# EJ8_LOGIC_SCH.net
KiCad netlist of a schematic drawn in Altium Designer
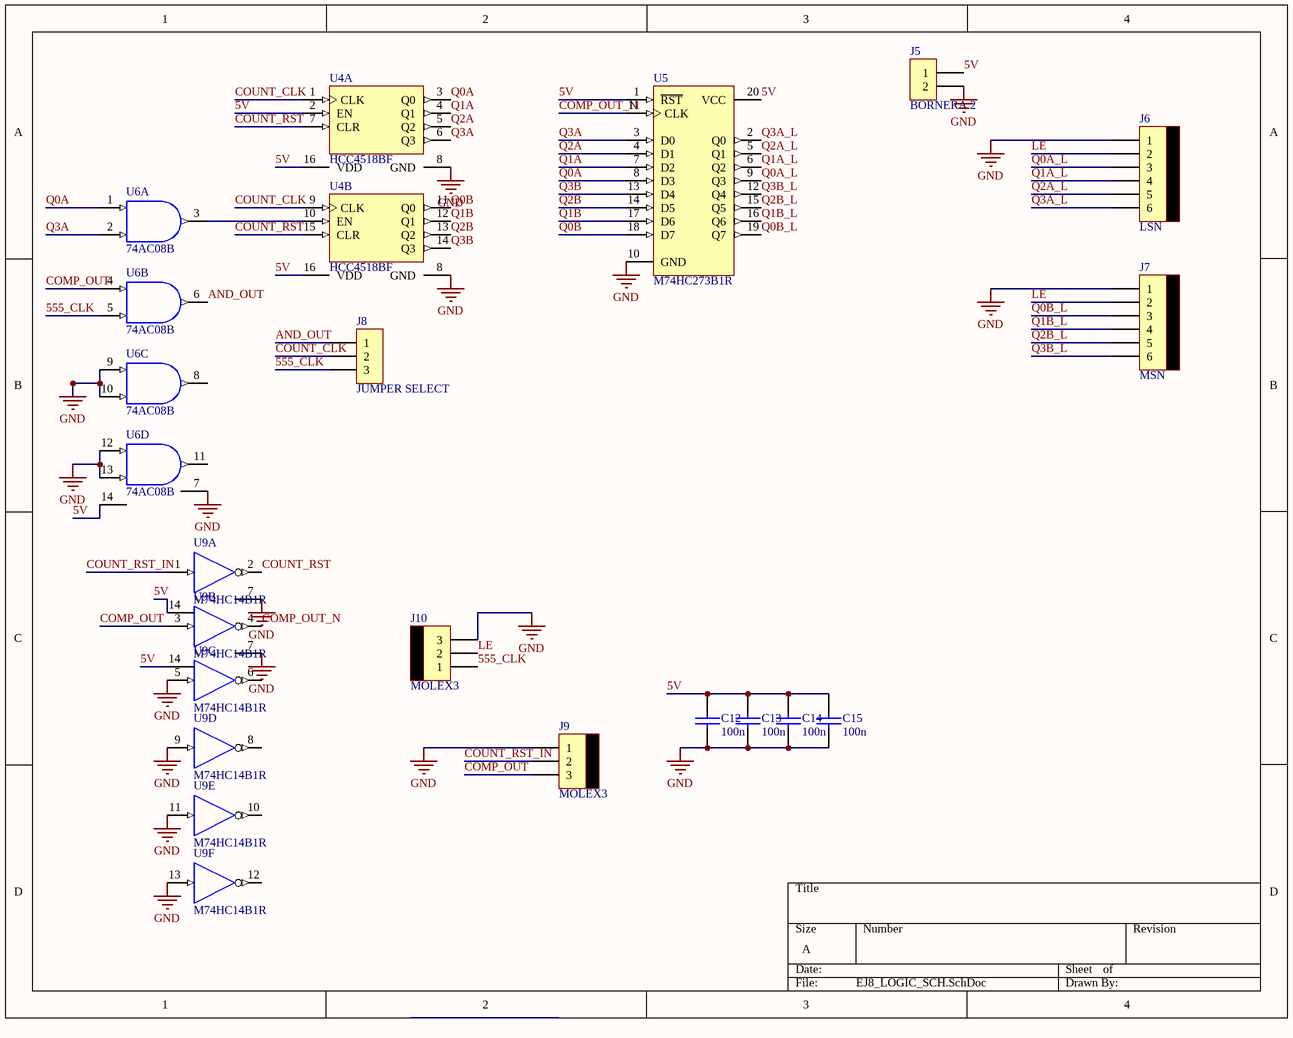
[diagram p0: EJ8_LOGIC_SCH.SchDoc]

(export (version "E")
  (design (tool "Eeschema 10.0.6"))
  (components
    (comp (ref "C12") (value "100n") (footprint "0805") (libsource (lib "LIBEBAL") (part "CAP")))
    (comp (ref "C13") (value "100n") (footprint "0805") (libsource (lib "LIBEBAL") (part "CAP")))
    (comp (ref "C14") (value "100n") (footprint "0805") (libsource (lib "LIBEBAL") (part "CAP")))
    (comp (ref "C15") (value "100n") (footprint "0805") (libsource (lib "LIBEBAL") (part "CAP")))
    (comp (ref "J5")
      (value "BORNERA 2")
      (footprint "BORNERA2")
      (libsource (lib "LIBEBAL") (part "BORNERA 2"))
    )
    (comp (ref "J6") (value "LSN") (footprint "MOLEX6") (libsource (lib "LIBEBAL") (part "MOLEX6")))
    (comp (ref "J7") (value "MSN") (footprint "MOLEX6") (libsource (lib "LIBEBAL") (part "MOLEX6")))
    (comp (ref "J8") (value "JUMPER SELECT") (footprint "SIP3") (libsource (lib "LIBEBAL") (part "CON3")))
    (comp (ref "J9") (value "MOLEX3") (footprint "MOLEX3") (libsource (lib "") (part "MOLEX3_1")))
    (comp (ref "J10") (value "MOLEX3") (footprint "MOLEX3") (libsource (lib "LIBEBAL") (part "MOLEX3")))
    (comp (ref "U4")
      (value "HCC4518BF")
      (footprint "DIP16")
      (description "Dual Decade Up-Counter")
      (fields (field (name "PUBLISHER") "Altium Limited"))
      (libsource (lib "ST Logic Counter") (part "HCC4518BF"))
    )
    (comp (ref "U5")
      (value "M74HC273B1R")
      (footprint "DIP20")
      (description "Octal D-Type Flip-Flop with Clear")
      (fields (field (name "PUBLISHER") "Altium Limited"))
      (libsource (lib "ST Logic Flip-Flop") (part "M74HC273B1R"))
    )
    (comp (ref "U6")
      (value "74AC08B")
      (footprint "DIP14")
      (description "Quad 2-Input AND Gate")
      (fields (field (name "PUBLISHER") "Altium Limited"))
      (libsource (lib "ST Logic Gate") (part "74AC08B"))
    )
    (comp (ref "U9")
      (value "M74HC14B1R")
      (footprint "DIP14")
      (description "Hex Schmitt Inverter")
      (fields (field (name "PUBLISHER") "Altium Limited"))
      (libsource (lib "ST Logic Gate") (part "M74HC14B1R"))
    )
  )
  (nets
    (net (code "1") (name "/555_CLK") (class "Default")
      (node (ref "J10") (pin "1") (pinfunction "1_1") (pintype "passive"))
      (node (ref "J8") (pin "3") (pinfunction "3_3") (pintype "passive"))
      (node (ref "U6") (pin "5") (pinfunction "B_5") (pintype "input"))
    )
    (net (code "2") (name "/AND_OUT") (class "Default")
      (node (ref "J8") (pin "1") (pinfunction "1_1") (pintype "passive"))
      (node (ref "U6") (pin "6") (pinfunction "Y_6") (pintype "output"))
    )
    (net (code "3") (name "/COMP_OUT") (class "Default")
      (node (ref "J9") (pin "3") (pinfunction "3_3") (pintype "passive"))
      (node (ref "U6") (pin "4") (pinfunction "A_4") (pintype "input"))
      (node (ref "U9") (pin "3") (pinfunction "A_3") (pintype "input"))
    )
    (net (code "4") (name "/COMP_OUT_N") (class "Default")
      (node (ref "U5") (pin "11") (pinfunction "CLK_11") (pintype "input"))
      (node (ref "U9") (pin "4") (pinfunction "Y_4") (pintype "output"))
    )
    (net (code "5") (name "/COUNT_CLK") (class "Default")
      (node (ref "J8") (pin "2") (pinfunction "2_2") (pintype "passive"))
      (node (ref "U4") (pin "1") (pinfunction "CLK_1") (pintype "input"))
      (node (ref "U4") (pin "9") (pinfunction "CLK_9") (pintype "input"))
    )
    (net (code "6") (name "/COUNT_RST") (class "Default")
      (node (ref "U4") (pin "15") (pinfunction "CLR_15") (pintype "input"))
      (node (ref "U4") (pin "7") (pinfunction "CLR_7") (pintype "input"))
      (node (ref "U9") (pin "2") (pinfunction "Y_2") (pintype "output"))
    )
    (net (code "7") (name "/COUNT_RST_IN") (class "Default")
      (node (ref "J9") (pin "2") (pinfunction "2_2") (pintype "passive"))
      (node (ref "U9") (pin "1") (pinfunction "A_1") (pintype "input"))
    )
    (net (code "8") (name "/LE") (class "Default")
      (node (ref "J10") (pin "2") (pinfunction "2_2") (pintype "passive"))
      (node (ref "J6") (pin "2") (pinfunction "2_2") (pintype "passive"))
      (node (ref "J7") (pin "2") (pinfunction "2_2") (pintype "passive"))
    )
    (net (code "9") (name "/Q0A") (class "Default")
      (node (ref "U4") (pin "3") (pinfunction "Q0_3") (pintype "output"))
      (node (ref "U5") (pin "8") (pinfunction "D3_8") (pintype "input"))
      (node (ref "U6") (pin "1") (pinfunction "A_1") (pintype "input"))
    )
    (net (code "10") (name "/Q0A_L") (class "Default")
      (node (ref "J6") (pin "3") (pinfunction "3_3") (pintype "passive"))
      (node (ref "U5") (pin "9") (pinfunction "Q3_9") (pintype "output"))
    )
    (net (code "11") (name "/Q0B") (class "Default")
      (node (ref "U4") (pin "11") (pinfunction "Q0_11") (pintype "output"))
      (node (ref "U5") (pin "18") (pinfunction "D7_18") (pintype "input"))
    )
    (net (code "12") (name "/Q0B_L") (class "Default")
      (node (ref "J7") (pin "3") (pinfunction "3_3") (pintype "passive"))
      (node (ref "U5") (pin "19") (pinfunction "Q7_19") (pintype "output"))
    )
    (net (code "13") (name "/Q1A") (class "Default")
      (node (ref "U4") (pin "4") (pinfunction "Q1_4") (pintype "output"))
      (node (ref "U5") (pin "7") (pinfunction "D2_7") (pintype "input"))
    )
    (net (code "14") (name "/Q1A_L") (class "Default")
      (node (ref "J6") (pin "4") (pinfunction "4_4") (pintype "passive"))
      (node (ref "U5") (pin "6") (pinfunction "Q2_6") (pintype "output"))
    )
    (net (code "15") (name "/Q1B") (class "Default")
      (node (ref "U4") (pin "12") (pinfunction "Q1_12") (pintype "output"))
      (node (ref "U5") (pin "17") (pinfunction "D6_17") (pintype "input"))
    )
    (net (code "16") (name "/Q1B_L") (class "Default")
      (node (ref "J7") (pin "4") (pinfunction "4_4") (pintype "passive"))
      (node (ref "U5") (pin "16") (pinfunction "Q6_16") (pintype "output"))
    )
    (net (code "17") (name "/Q2A") (class "Default")
      (node (ref "U4") (pin "5") (pinfunction "Q2_5") (pintype "output"))
      (node (ref "U5") (pin "4") (pinfunction "D1_4") (pintype "input"))
    )
    (net (code "18") (name "/Q2A_L") (class "Default")
      (node (ref "J6") (pin "5") (pinfunction "5_5") (pintype "passive"))
      (node (ref "U5") (pin "5") (pinfunction "Q1_5") (pintype "output"))
    )
    (net (code "19") (name "/Q2B") (class "Default")
      (node (ref "U4") (pin "13") (pinfunction "Q2_13") (pintype "output"))
      (node (ref "U5") (pin "14") (pinfunction "D5_14") (pintype "input"))
    )
    (net (code "20") (name "/Q2B_L") (class "Default")
      (node (ref "J7") (pin "5") (pinfunction "5_5") (pintype "passive"))
      (node (ref "U5") (pin "15") (pinfunction "Q5_15") (pintype "output"))
    )
    (net (code "21") (name "/Q3A") (class "Default")
      (node (ref "U4") (pin "6") (pinfunction "Q3_6") (pintype "output"))
      (node (ref "U5") (pin "3") (pinfunction "D0_3") (pintype "input"))
      (node (ref "U6") (pin "2") (pinfunction "B_2") (pintype "input"))
    )
    (net (code "22") (name "/Q3A_L") (class "Default")
      (node (ref "J6") (pin "6") (pinfunction "6_6") (pintype "passive"))
      (node (ref "U5") (pin "2") (pinfunction "Q0_2") (pintype "output"))
    )
    (net (code "23") (name "/Q3B") (class "Default")
      (node (ref "U4") (pin "14") (pinfunction "Q3_14") (pintype "output"))
      (node (ref "U5") (pin "13") (pinfunction "D4_13") (pintype "input"))
    )
    (net (code "24") (name "/Q3B_L") (class "Default")
      (node (ref "J7") (pin "6") (pinfunction "6_6") (pintype "passive"))
      (node (ref "U5") (pin "12") (pinfunction "Q4_12") (pintype "output"))
    )
    (net (code "25") (name "GND") (class "Default")
      (node (ref "C12") (pin "2") (pinfunction "2_2") (pintype "passive"))
      (node (ref "C13") (pin "2") (pinfunction "2_2") (pintype "passive"))
      (node (ref "C14") (pin "2") (pinfunction "2_2") (pintype "passive"))
      (node (ref "C15") (pin "2") (pinfunction "2_2") (pintype "passive"))
      (node (ref "J10") (pin "3") (pinfunction "3_3") (pintype "passive"))
      (node (ref "J5") (pin "2") (pinfunction "2_2") (pintype "passive"))
      (node (ref "J6") (pin "1") (pinfunction "1_1") (pintype "passive"))
      (node (ref "J7") (pin "1") (pinfunction "1_1") (pintype "passive"))
      (node (ref "J9") (pin "1") (pinfunction "1_1") (pintype "passive"))
      (node (ref "U4") (pin "8") (pinfunction "GND_8") (pintype "power_in"))
      (node (ref "U5") (pin "10") (pinfunction "GND_10") (pintype "power_in"))
      (node (ref "U6") (pin "10") (pinfunction "B_10") (pintype "input"))
      (node (ref "U6") (pin "12") (pinfunction "A_12") (pintype "input"))
      (node (ref "U6") (pin "13") (pinfunction "B_13") (pintype "input"))
      (node (ref "U6") (pin "7") (pinfunction "GND_7") (pintype "power_in"))
      (node (ref "U6") (pin "9") (pinfunction "A_9") (pintype "input"))
      (node (ref "U9") (pin "11") (pinfunction "A_11") (pintype "input"))
      (node (ref "U9") (pin "13") (pinfunction "A_13") (pintype "input"))
      (node (ref "U9") (pin "5") (pinfunction "A_5") (pintype "input"))
      (node (ref "U9") (pin "7") (pinfunction "GND_7") (pintype "power_in"))
      (node (ref "U9") (pin "9") (pinfunction "A_9") (pintype "input"))
    )
    (net (code "26") (name "Net-(U4B-EN)") (class "Default")
      (node (ref "U4") (pin "10") (pinfunction "EN_10") (pintype "input"))
      (node (ref "U6") (pin "3") (pinfunction "Y_3") (pintype "output"))
    )
    (net (code "27") (name "VCC") (class "Default")
      (node (ref "C12") (pin "1") (pinfunction "1_1") (pintype "passive"))
      (node (ref "C13") (pin "1") (pinfunction "1_1") (pintype "passive"))
      (node (ref "C14") (pin "1") (pinfunction "1_1") (pintype "passive"))
      (node (ref "C15") (pin "1") (pinfunction "1_1") (pintype "passive"))
      (node (ref "J5") (pin "1") (pinfunction "1_1") (pintype "passive"))
      (node (ref "U4") (pin "16") (pinfunction "VDD_16") (pintype "power_in"))
      (node (ref "U4") (pin "2") (pinfunction "EN_2") (pintype "input"))
      (node (ref "U5") (pin "1") (pinfunction "~{RST}_1") (pintype "input"))
      (node (ref "U5") (pin "20") (pinfunction "VCC_20") (pintype "power_in"))
      (node (ref "U6") (pin "14") (pinfunction "VCC_14") (pintype "power_in"))
      (node (ref "U9") (pin "14") (pinfunction "VCC_14") (pintype "power_in"))
    )
    (net (code "28") (name "unconnected-(U6C-Y-Pad8)") (class "Default")
      (node (ref "U6") (pin "8") (pinfunction "Y_8") (pintype "output"))
    )
    (net (code "29") (name "unconnected-(U6D-Y-Pad11)") (class "Default")
      (node (ref "U6") (pin "11") (pinfunction "Y_11") (pintype "output"))
    )
    (net (code "30") (name "unconnected-(U9C-Y-Pad6)") (class "Default")
      (node (ref "U9") (pin "6") (pinfunction "Y_6") (pintype "output"))
    )
    (net (code "31") (name "unconnected-(U9D-Y-Pad8)") (class "Default")
      (node (ref "U9") (pin "8") (pinfunction "Y_8") (pintype "output"))
    )
    (net (code "32") (name "unconnected-(U9E-Y-Pad10)") (class "Default")
      (node (ref "U9") (pin "10") (pinfunction "Y_10") (pintype "output"))
    )
    (net (code "33") (name "unconnected-(U9F-Y-Pad12)") (class "Default")
      (node (ref "U9") (pin "12") (pinfunction "Y_12") (pintype "output"))
    )
  )
)
